# CruiseControlSystemWiringDiagram.net
KiCad netlist of a schematic drawn in EasyEDA
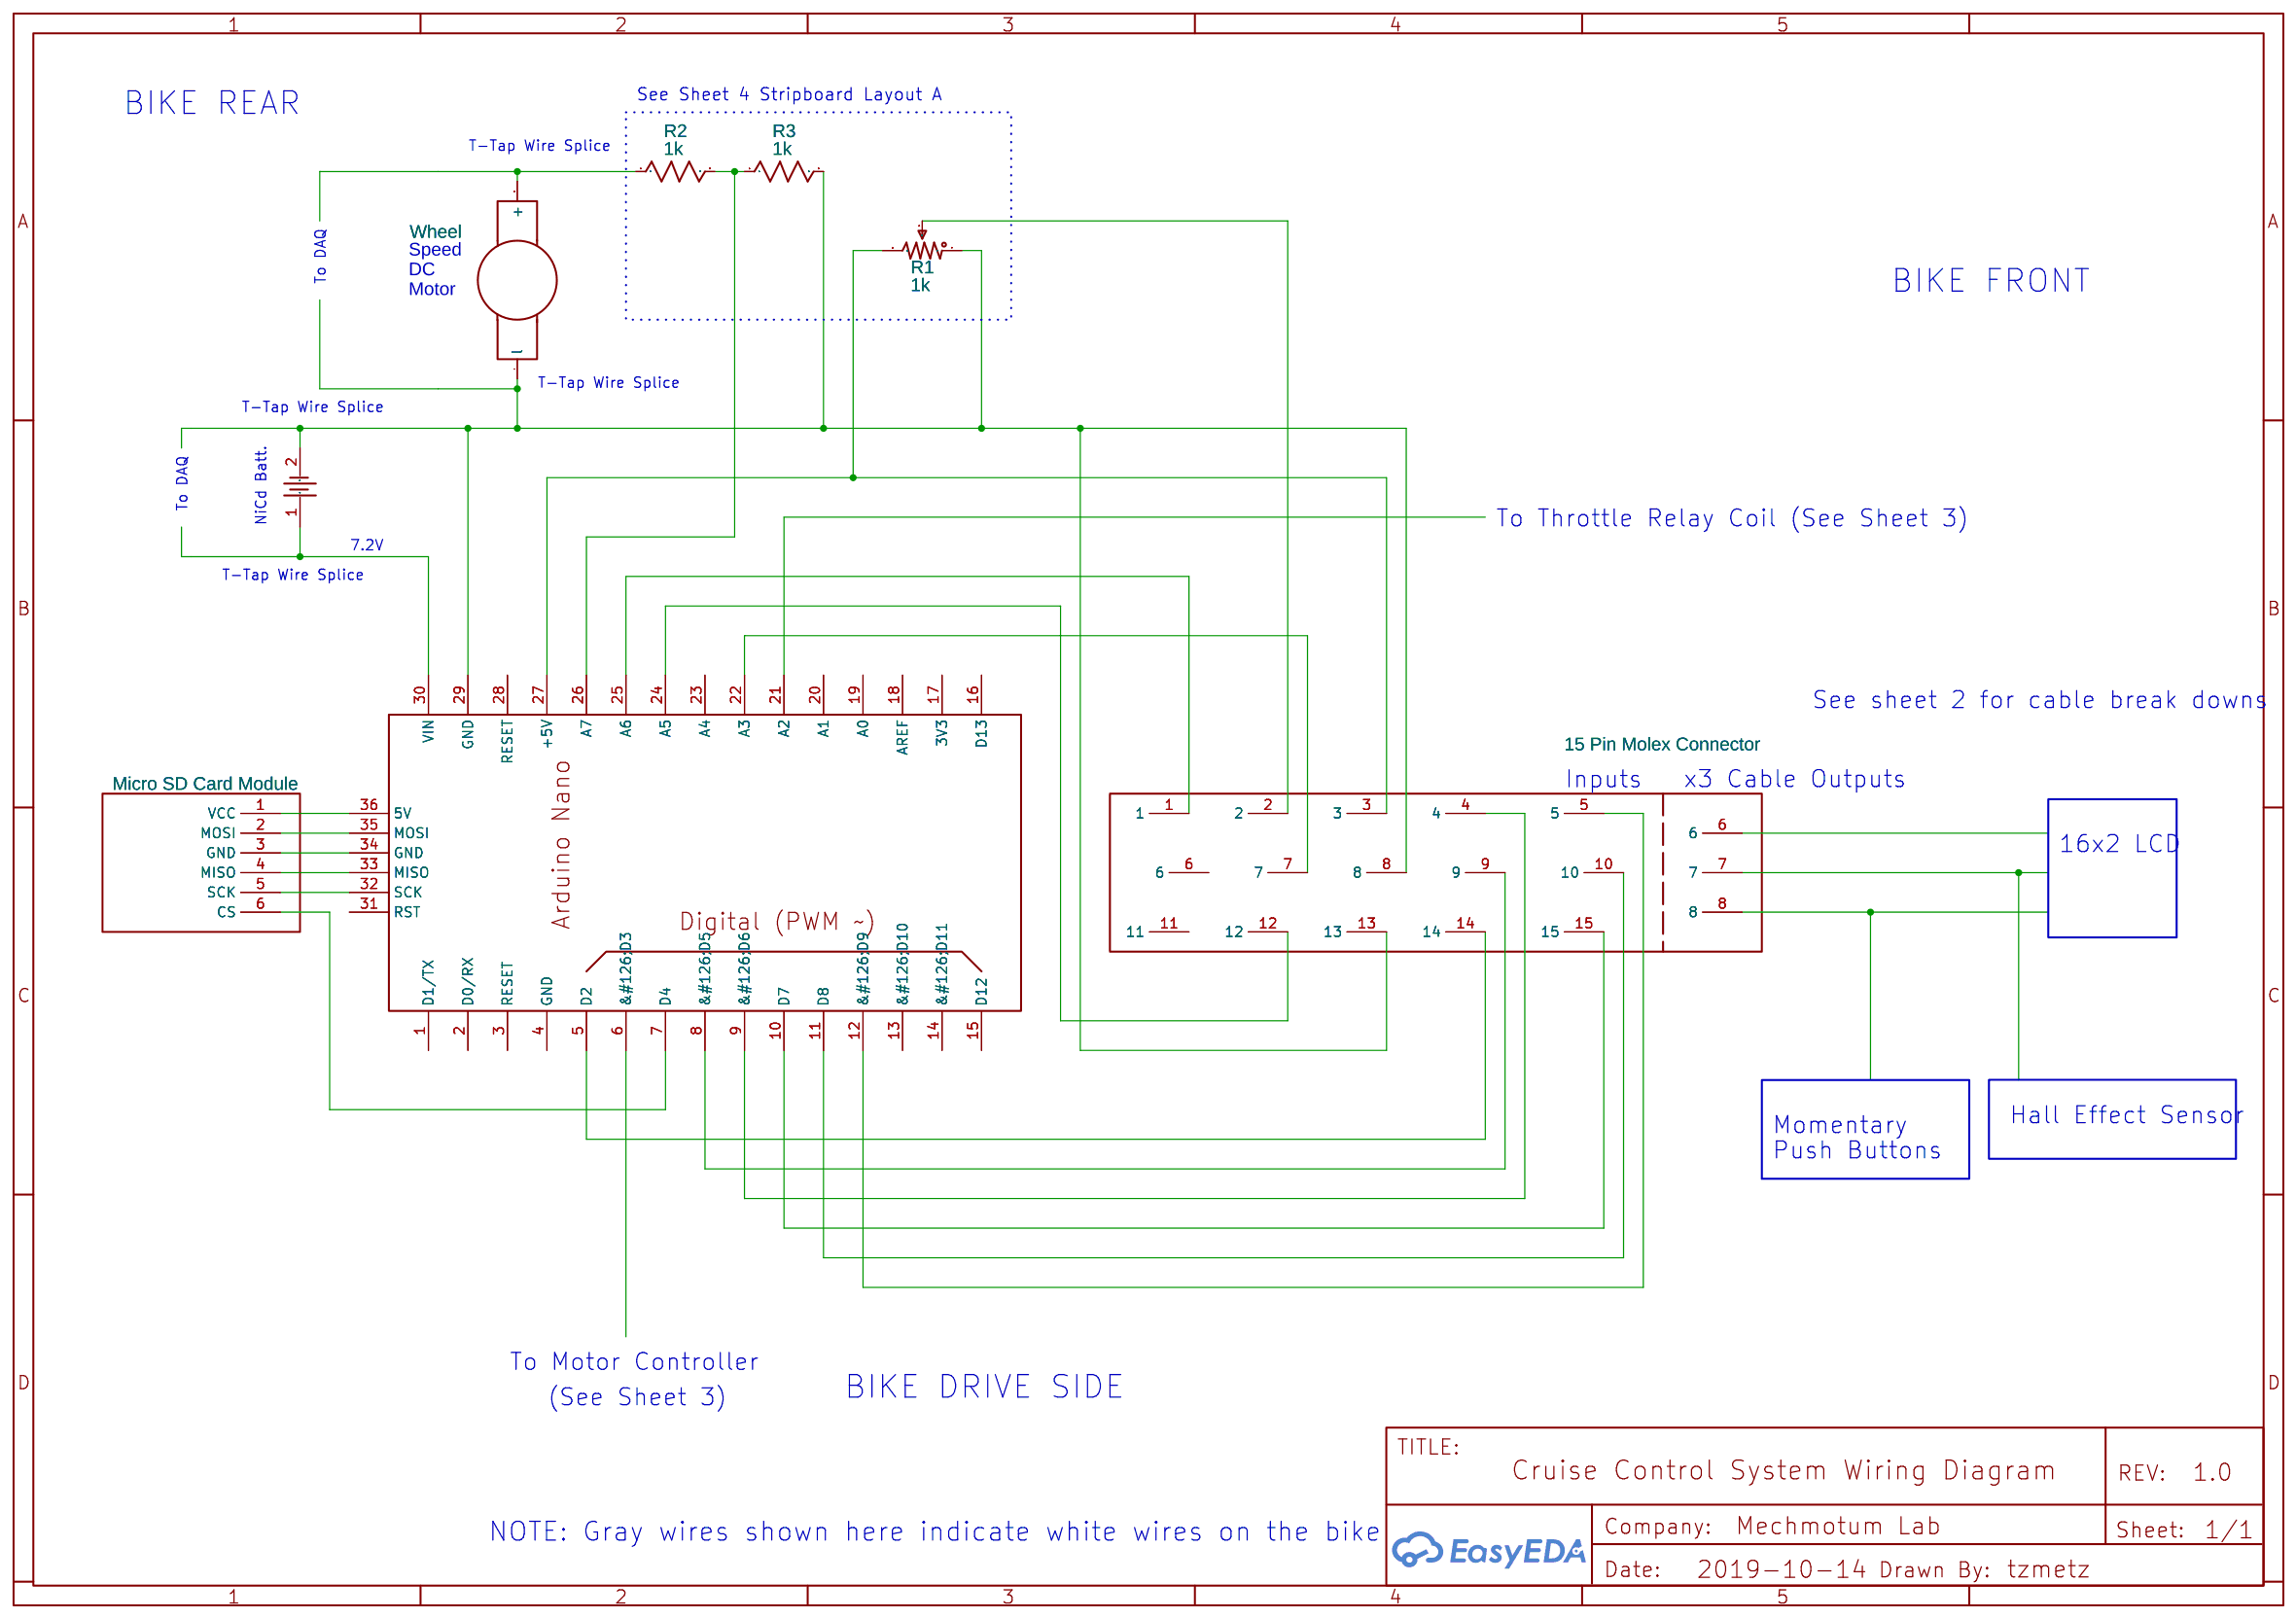
[diagram p0: Sheet_1]
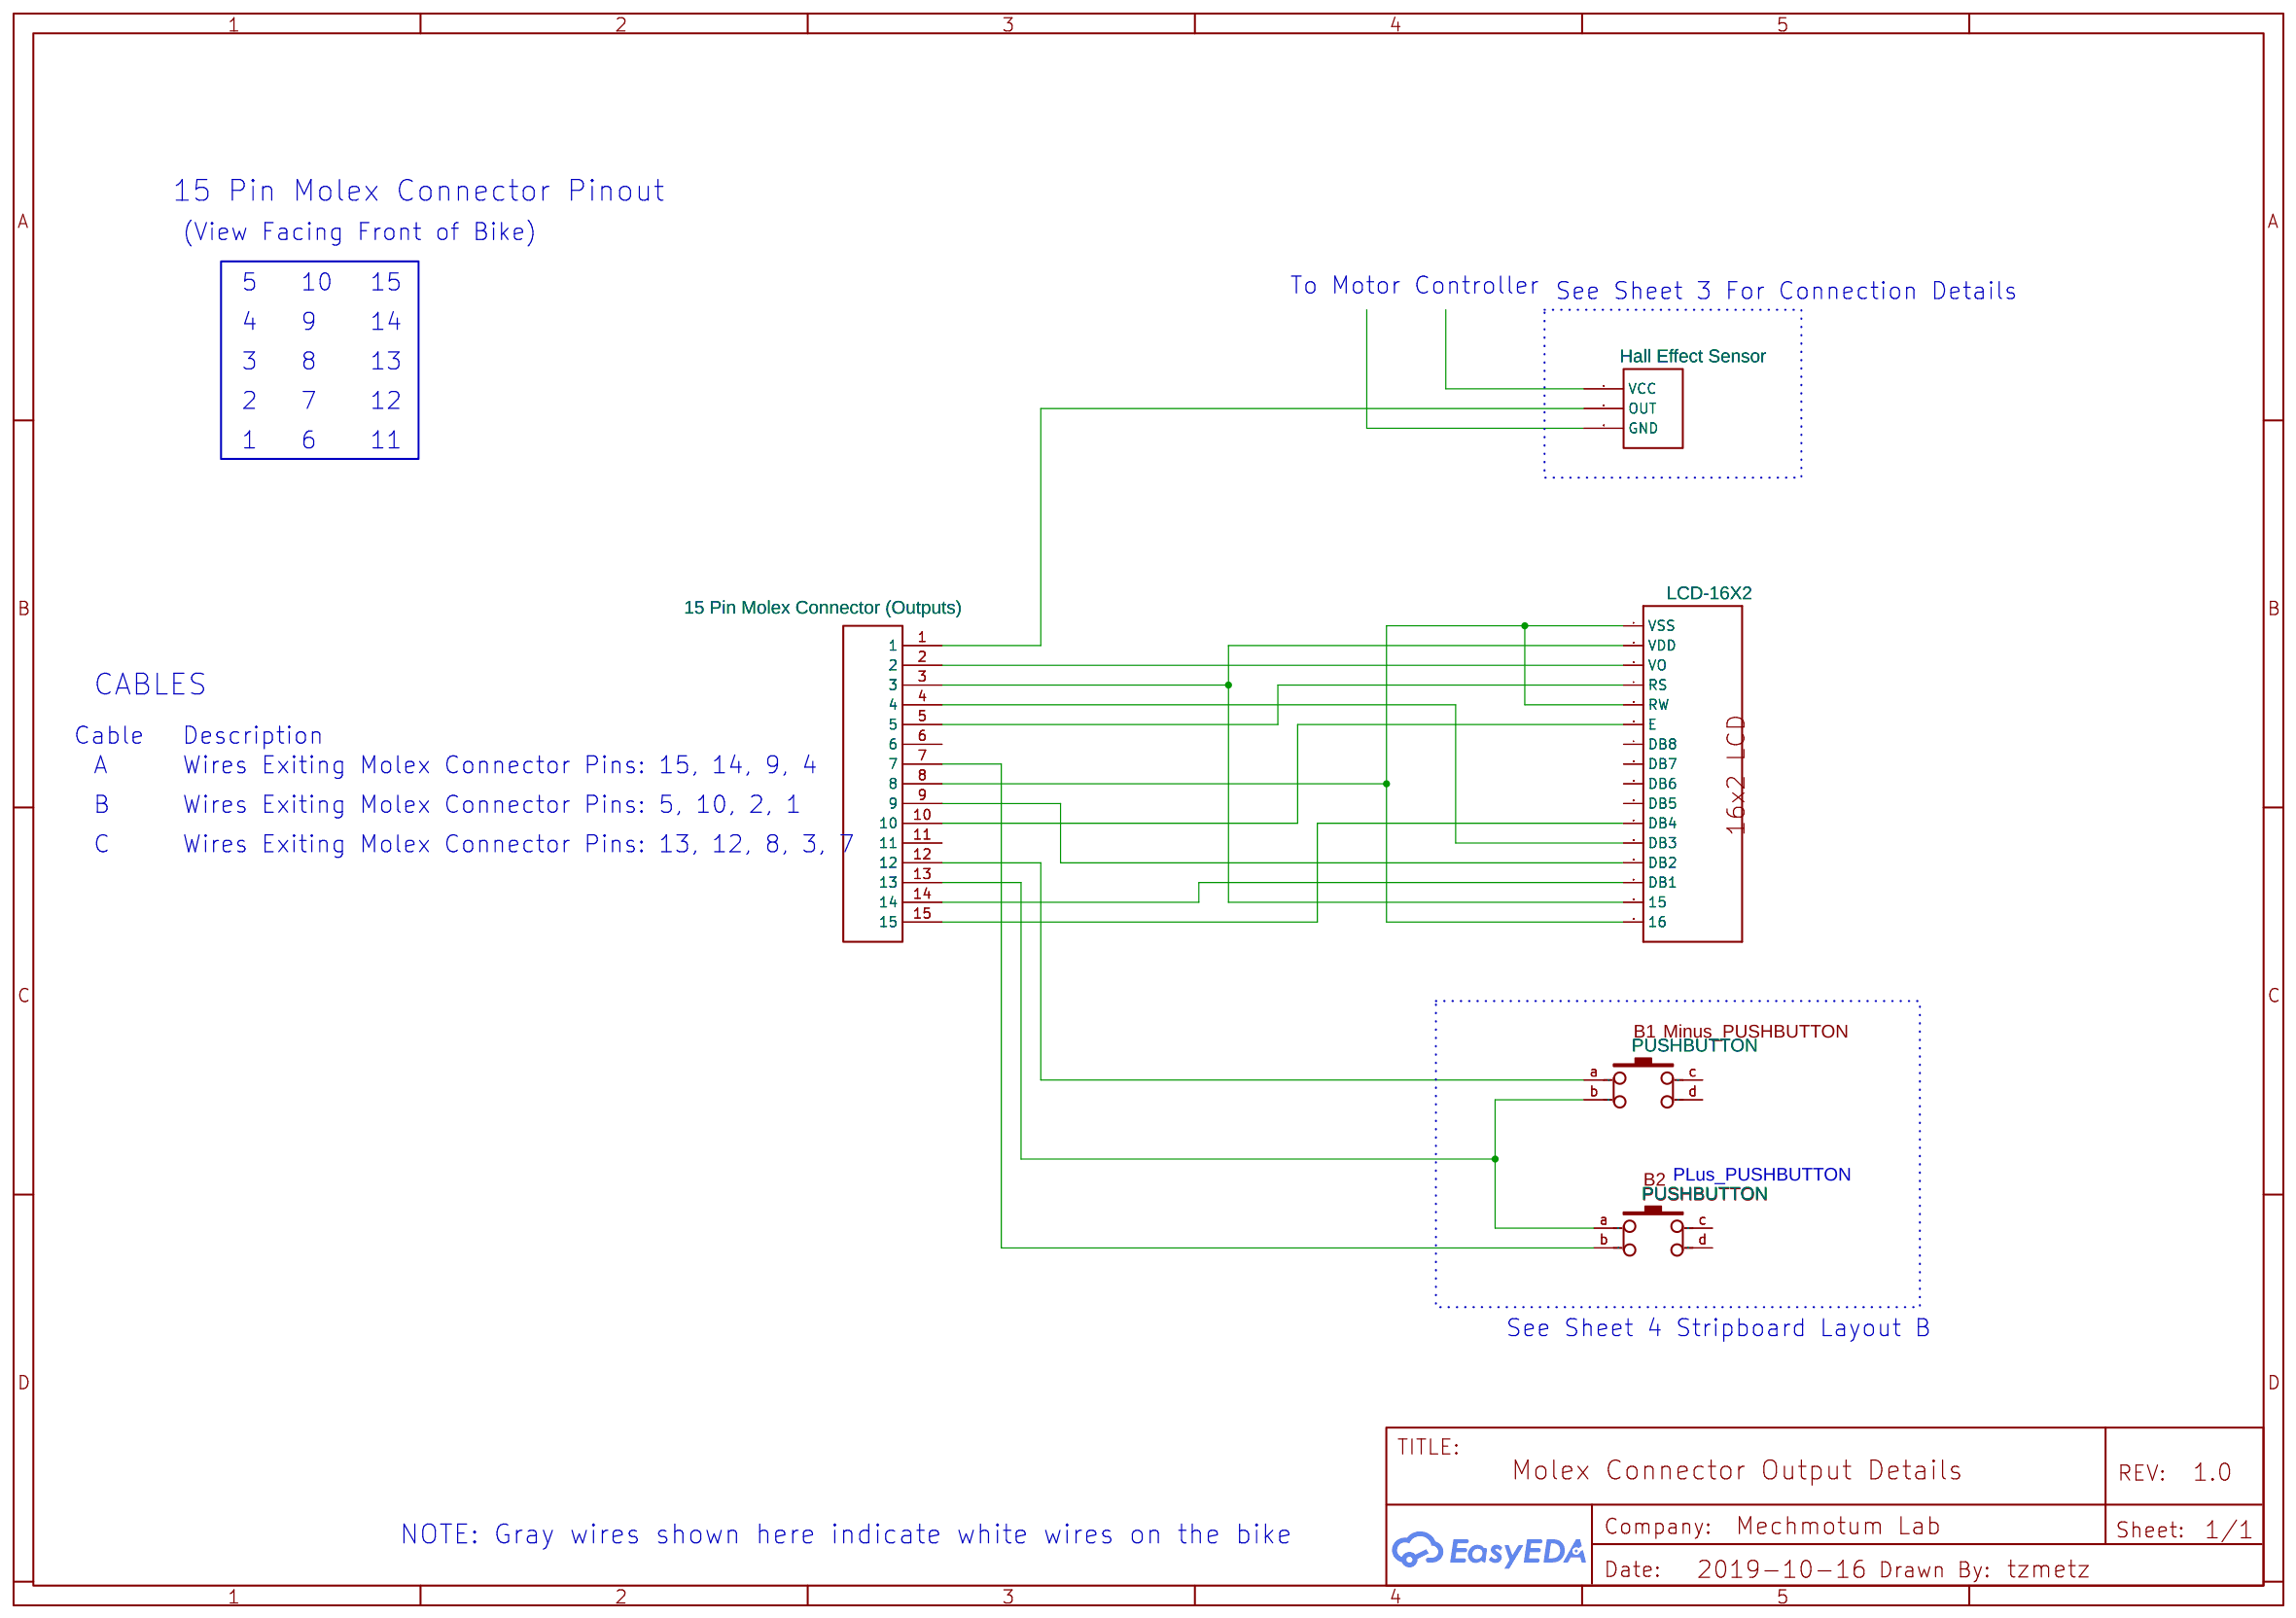
[diagram p1: Sheet_2]
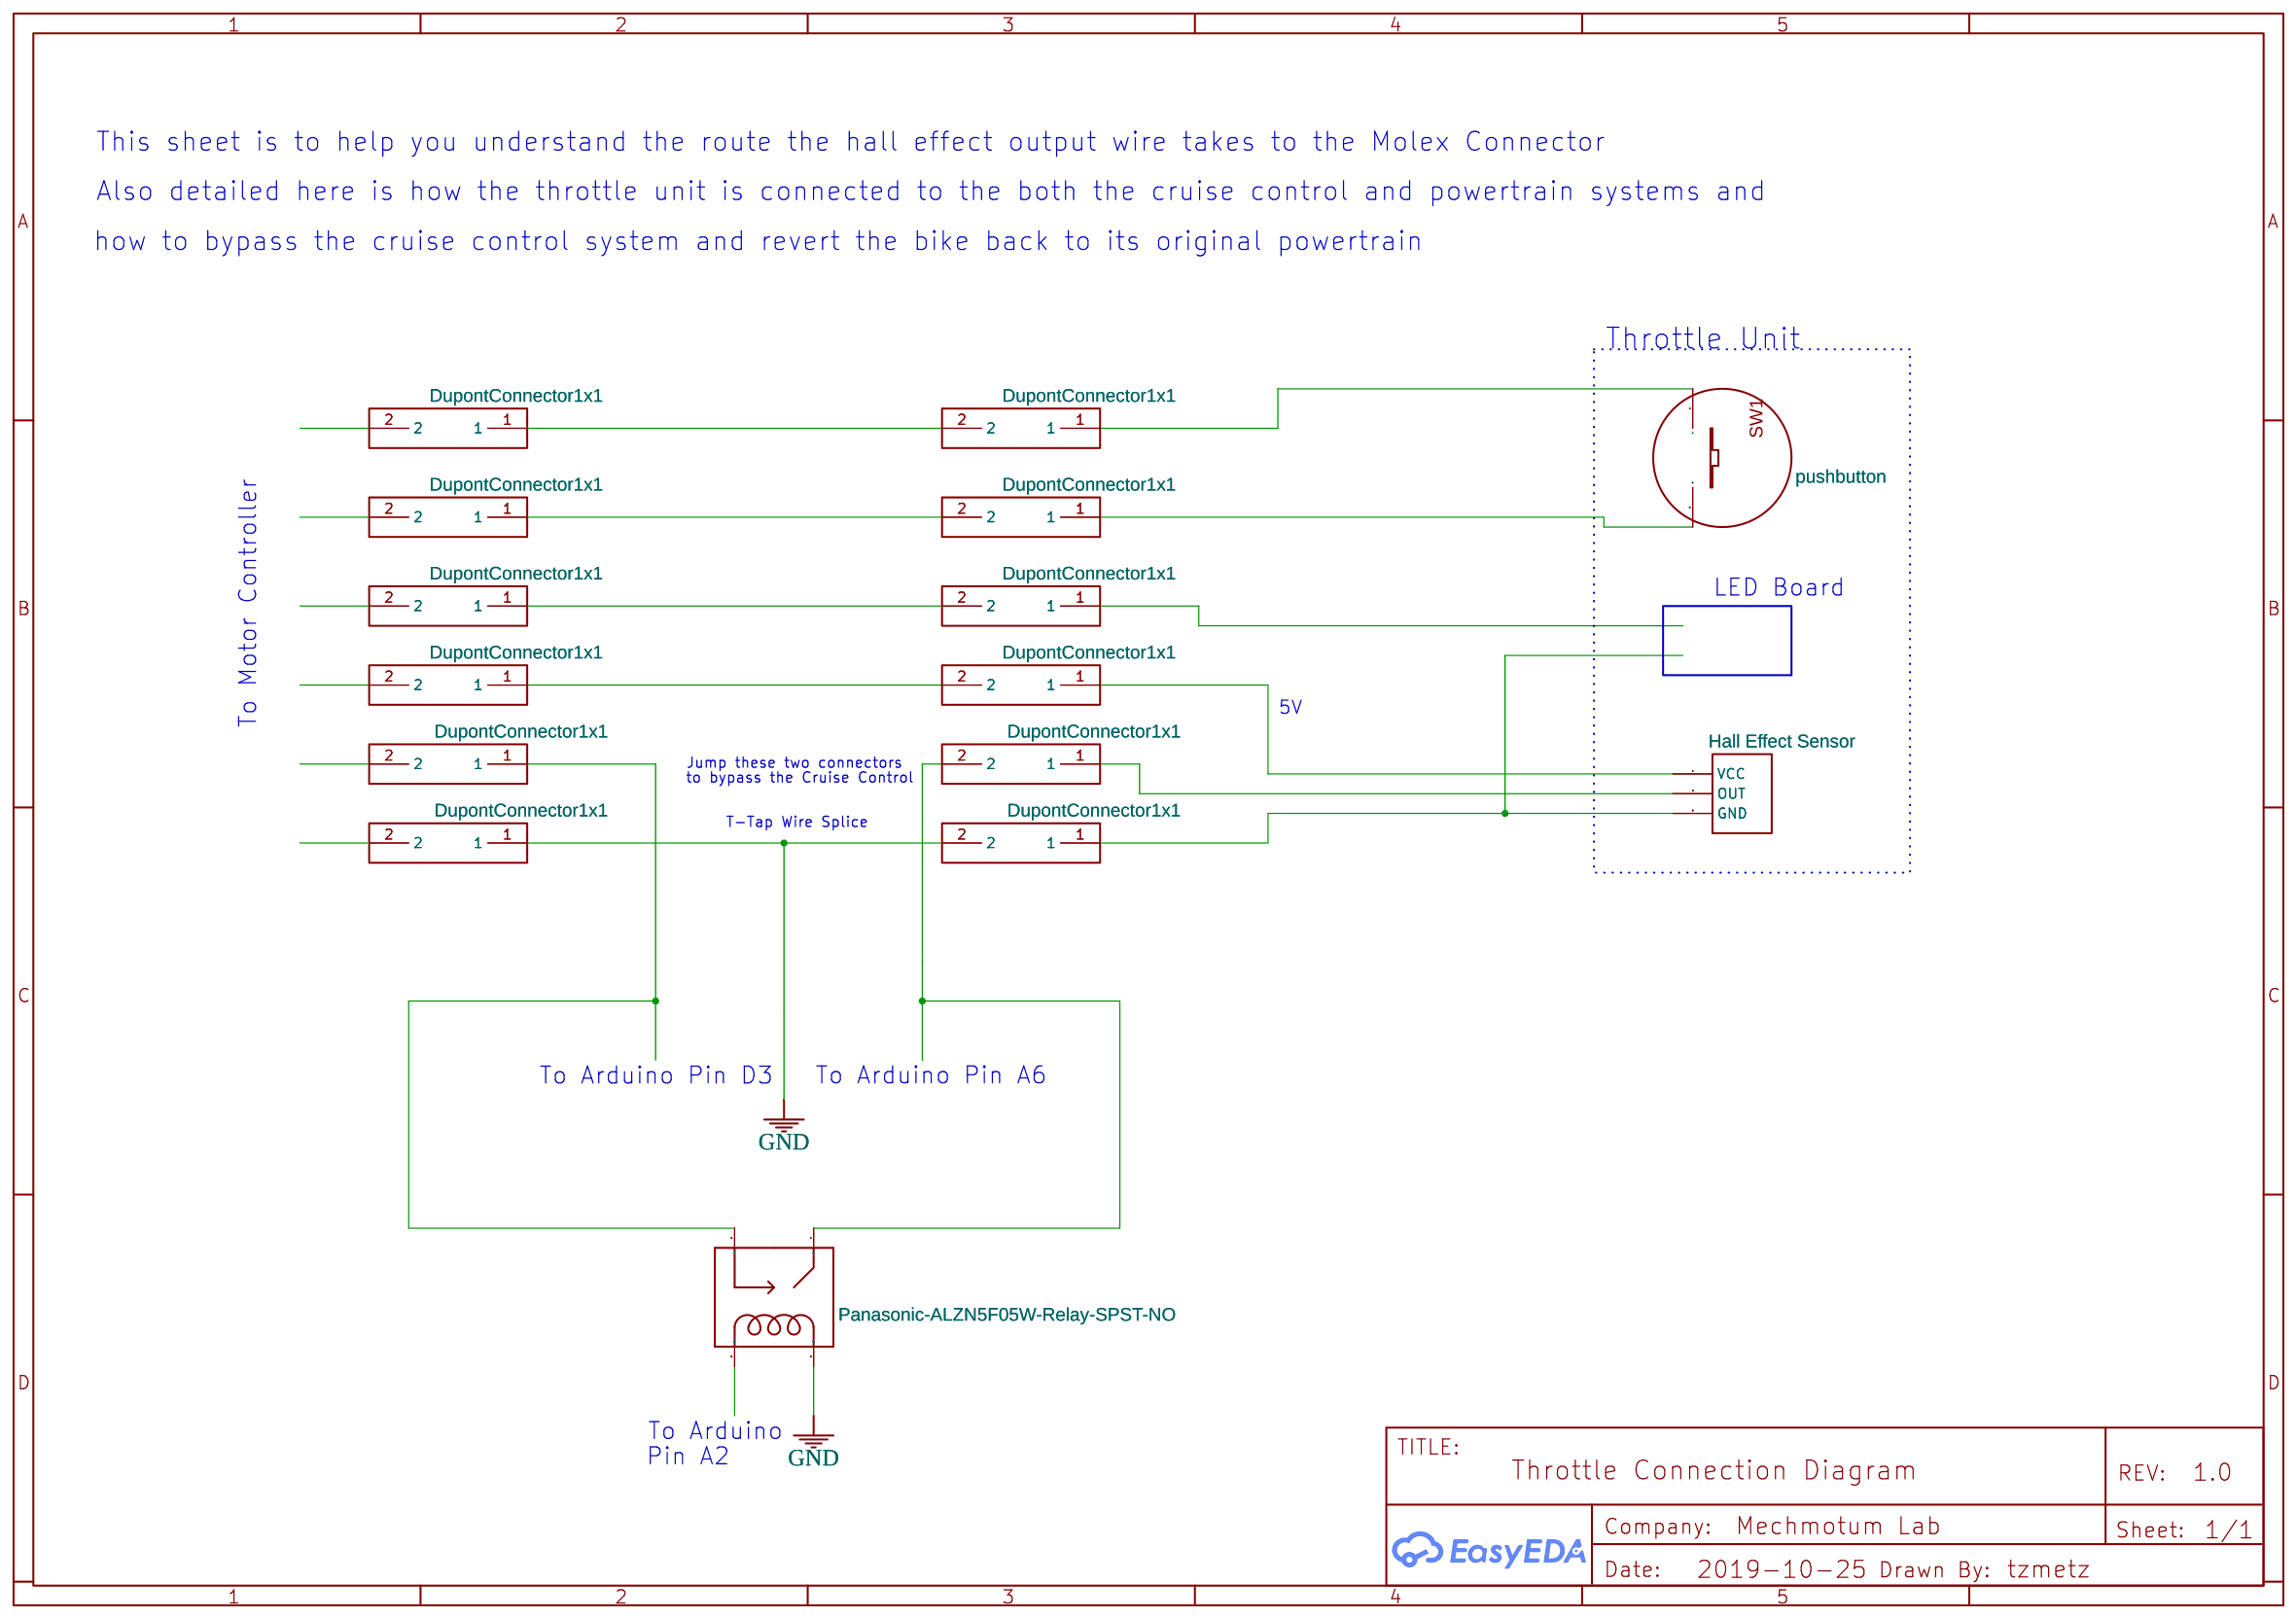
[diagram p2: Sheet_3]
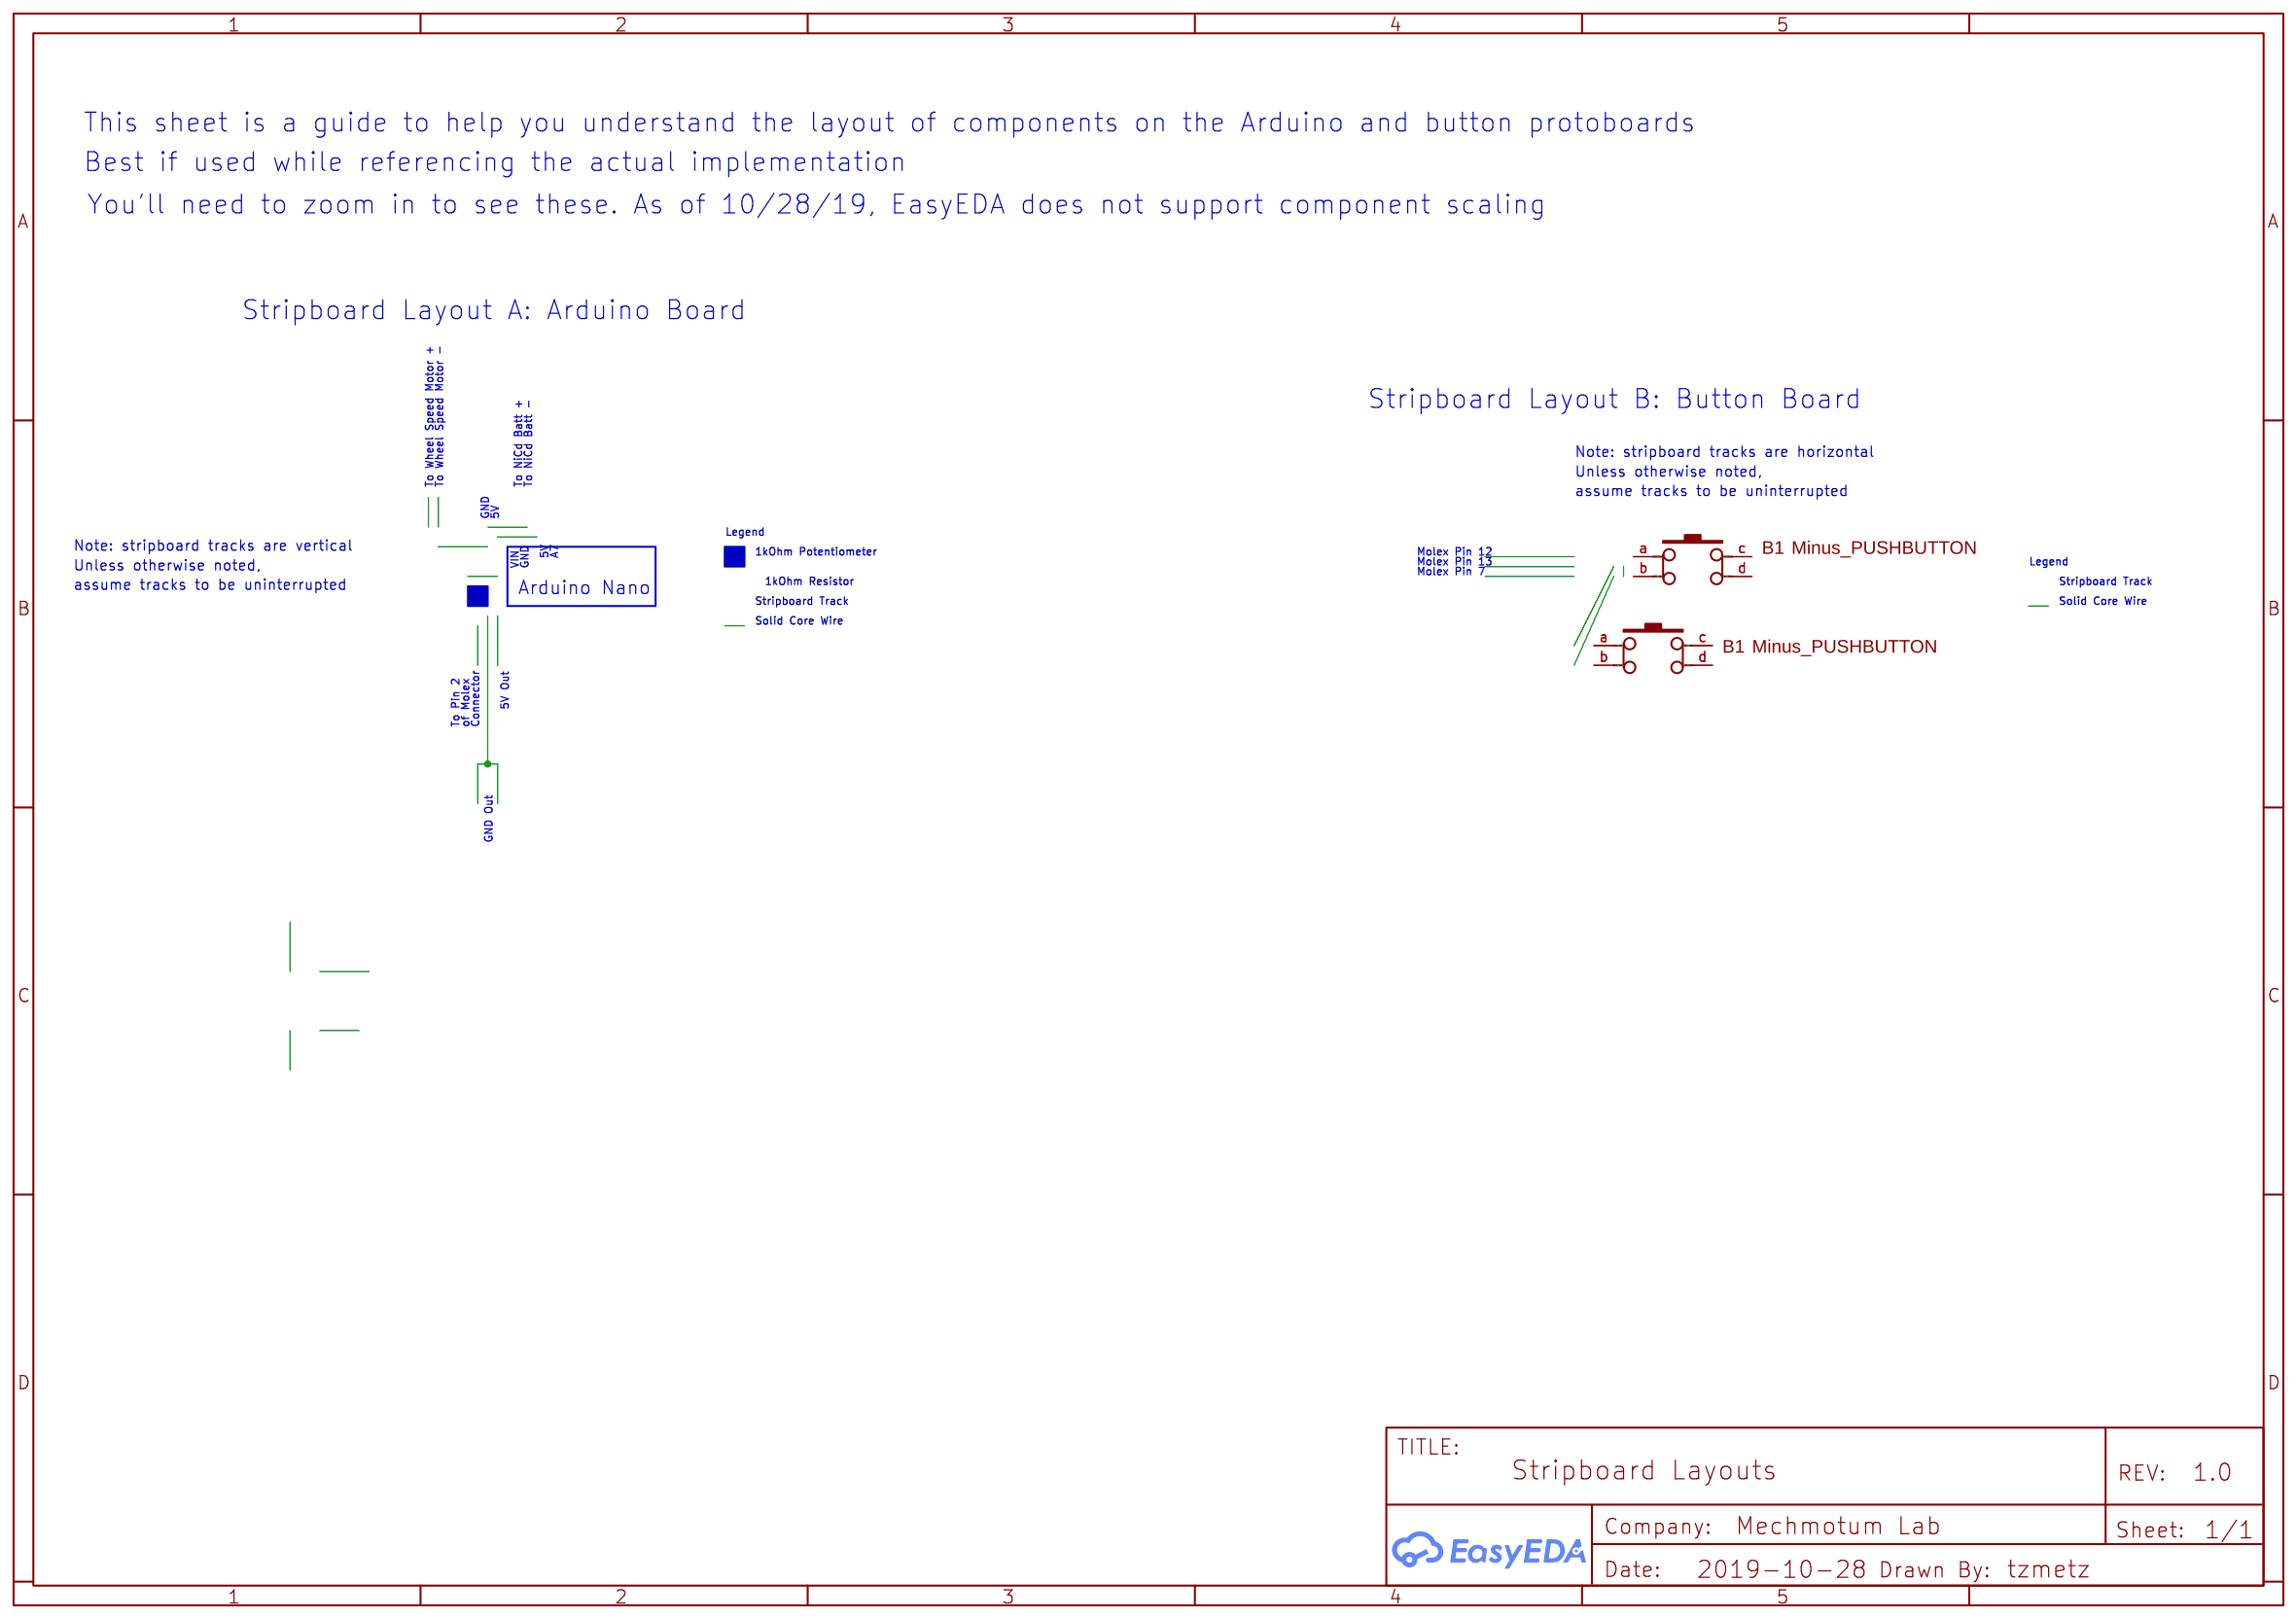
[diagram p3: Sheet_4]
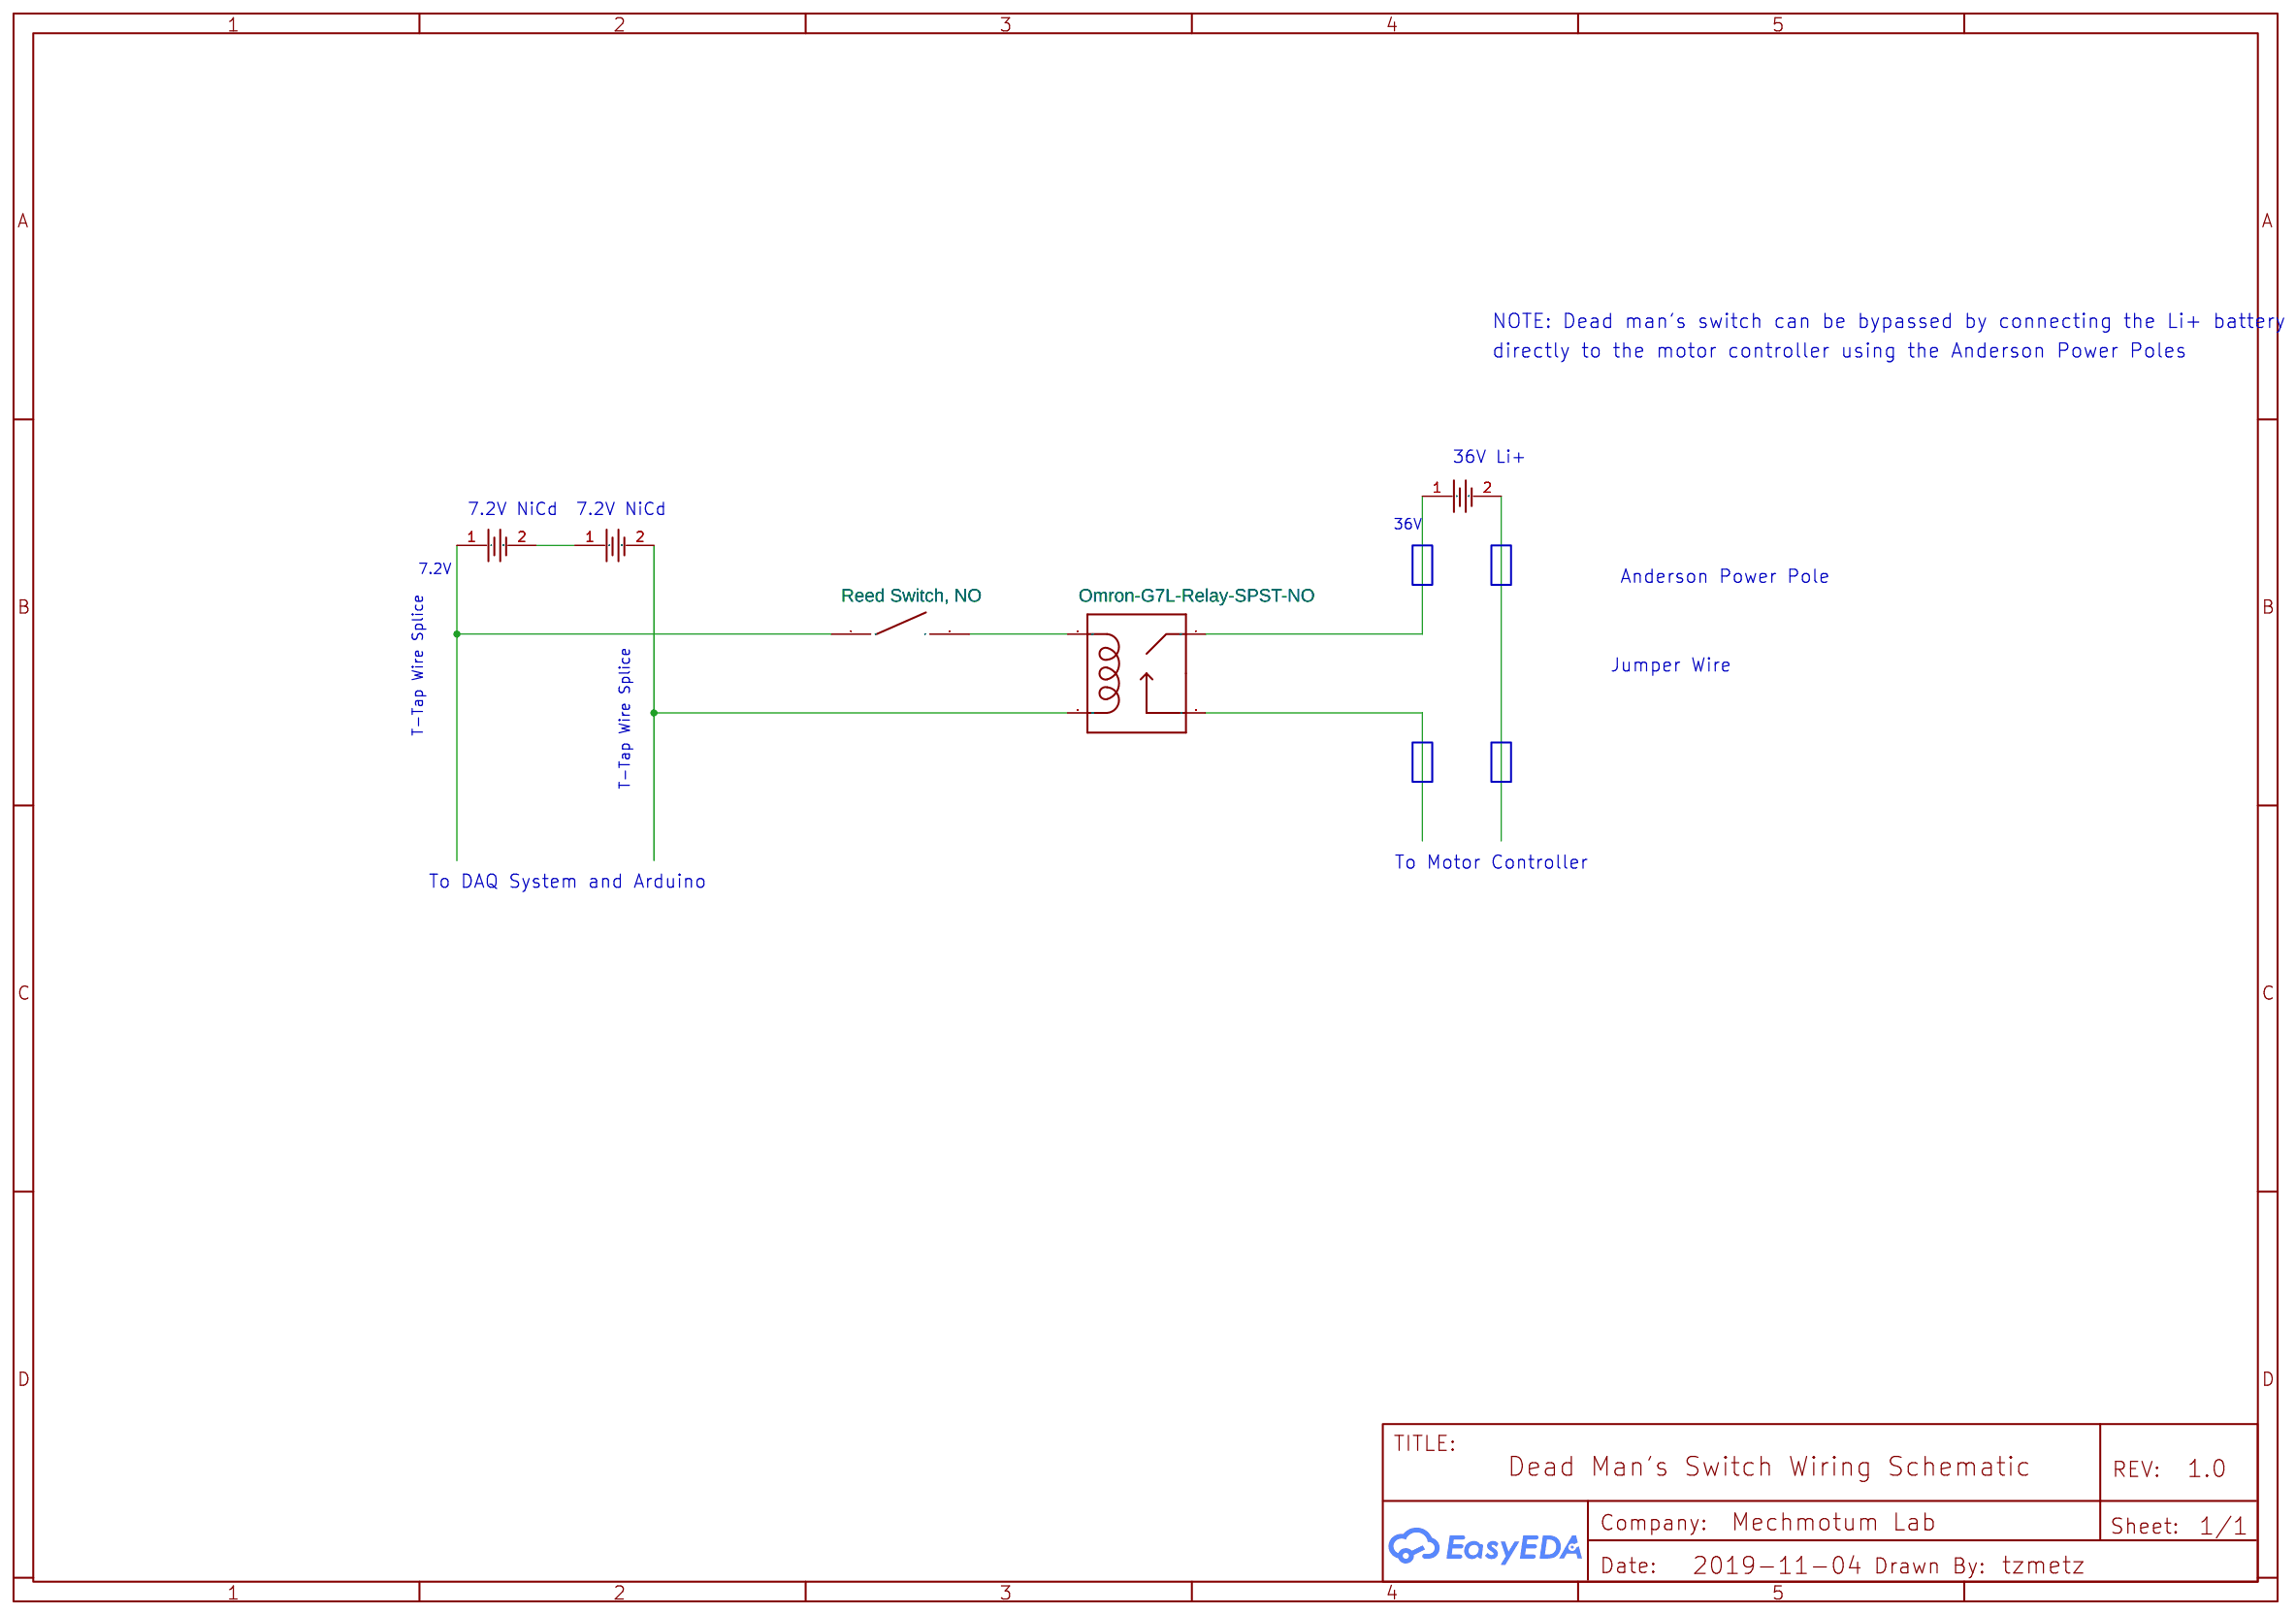
[diagram p4: Sheet_5]

(export (version "E")
  (design (tool "Eeschema 10.0.6"))
  (components
    (comp (ref "B1")
      (value "NiCd Battery 7.2V Line")
      (fields (field (name "BOM_Manufacturer Part") "BS-2-1") (field (name "BOM_Supplier Part") "C70376"))
      (libsource (lib "") (part "Unknown_145_240"))
    )
    (comp (ref "R1")
      (value "1k")
      (fields
        (field (name "BOM_Manufacturer Part") "3386P-1-101LF")
        (field (name "BOM_Supplier Part") "C125022")
      )
      (libsource (lib "") (part "3386P-1-101LF_US"))
    )
    (comp (ref "R2") (value "1k") (libsource (lib "") (part "Res_AXIAL-0.3(1/8W)_US")))
    (comp (ref "R3") (value "1k") (libsource (lib "") (part "Res_AXIAL-0.3(1/8W)_US")))
    (comp (ref "U2")
      (value "ARDUINO_NANO COPY")
      (fields (field (name "BOM_Manufacturer Part") "ARDUINO_NANO_LIVETHINGS"))
      (libsource (lib "") (part "Unknown_350_425"))
    )
    (comp (ref "U5") (value "Wheel") (libsource (lib "") (part "Unknown_255_135")))
    (comp (ref "U8") (value "Micro SD Card Module") (libsource (lib "") (part "Unknown_105_425")))
    (comp (ref "U10") (value "15 Pin Molex Connector") (libsource (lib "") (part "Unknown_635_435")))
    (comp (ref "U1") (value "PUSHBUTTON") (libsource (lib "") (part "Unknown_860_635")))
    (comp (ref "U6") (value "15 Pin Molex Connector (Outputs)") (libsource (lib "") (part "Unknown_450_310")))
    (comp (ref "U11") (value "LCD-16X2") (libsource (lib "") (part "Unknown_845_385")))
    (comp (ref "U12") (value "PUSHBUTTON") (libsource (lib "") (part "Unknown_855_560")))
    (comp (ref "U13") (value "Hall Effect Sensor") (libsource (lib "") (part "Unknown_795_180")))
    (comp (ref "RL2")
      (value "Panasonic-ALZN5F05W-Relay-SPST-NO")
      (libsource (lib "") (part "Unknown_385_645"))
    )
    (comp (ref "U3")
      (value "pushbutton")
      (fields (field (name "BOM_Manufacturer Part") "push button"))
      (libsource (lib "") (part "Unknown_875_220"))
    )
    (comp (ref "U4") (value "Hall Effect Sensor") (libsource (lib "") (part "Unknown_840_375")))
    (comp (ref "U7") (value "DupontConnector1x1") (libsource (lib "") (part "Unknown_510_380")))
    (comp (ref "U9") (value "DupontConnector1x1") (libsource (lib "") (part "Unknown_510_420")))
    (comp (ref "U14") (value "DupontConnector1x1") (libsource (lib "") (part "Unknown_510_300")))
    (comp (ref "U15") (value "DupontConnector1x1") (libsource (lib "") (part "Unknown_510_340")))
    (comp (ref "U16") (value "DupontConnector1x1") (libsource (lib "") (part "Unknown_510_255")))
    (comp (ref "U17") (value "DupontConnector1x1") (libsource (lib "") (part "Unknown_510_210")))
    (comp (ref "U18") (value "DupontConnector1x1") (libsource (lib "") (part "Unknown_220_210")))
    (comp (ref "U19") (value "DupontConnector1x1") (libsource (lib "") (part "Unknown_220_255")))
    (comp (ref "U20") (value "DupontConnector1x1") (libsource (lib "") (part "Unknown_220_340")))
    (comp (ref "U21") (value "DupontConnector1x1") (libsource (lib "") (part "Unknown_220_300")))
    (comp (ref "U22") (value "DupontConnector1x1") (libsource (lib "") (part "Unknown_220_420")))
    (comp (ref "U23") (value "DupontConnector1x1") (libsource (lib "") (part "Unknown_220_380")))
    (comp (ref "U24") (value "PUSHBUTTON") (libsource (lib "") (part "Unknown_880_295")))
    (comp (ref "U25") (value "PUSHBUTTON") (libsource (lib "") (part "Unknown_860_340")))
    (comp (ref "B2")
      (value "BS-2-1")
      (fields (field (name "BOM_Supplier Part") "C70376"))
      (libsource (lib "") (part "Unknown_245_270"))
    )
    (comp (ref "B3")
      (value "BS-2-1")
      (fields (field (name "BOM_Supplier Part") "C70376"))
      (libsource (lib "") (part "Unknown_305_270"))
    )
    (comp (ref "B4")
      (value "BS-2-1")
      (fields (field (name "BOM_Supplier Part") "C70376"))
      (libsource (lib "") (part "Unknown_735_245"))
    )
    (comp (ref "RL1") (value "Omron-G7L-Relay-SPST-NO") (libsource (lib "") (part "Unknown_575_335")))
    (comp (ref "SW1")
      (value "Reed Switch, NO")
      (fields (field (name "BOM_Manufacturer Part") "EVQ22705R") (field (name "BOM_Supplier Part") "C79156"))
      (libsource (lib "") (part "Unknown_450_315"))
    )
  )
  (nets
    (net (code "1") (name "GND") (class "Default")
      (node (ref "RL2") (pin "2") (pinfunction "COIL2_2") (pintype "unspecified"))
      (node (ref "U22") (pin "1") (pinfunction "1_1") (pintype "unspecified"))
      (node (ref "U9") (pin "2") (pinfunction "2_2") (pintype "unspecified"))
    )
    (net (code "2") (name "Net-(B2-Pad1)") (class "Default")
      (node (ref "B2") (pin "1") (pinfunction "1_1") (pintype "input"))
      (node (ref "SW1") (pin "1") (pinfunction "1_1") (pintype "input"))
    )
    (net (code "3") (name "Net-(B2-Pad2)") (class "Default")
      (node (ref "B2") (pin "2") (pinfunction "2_2") (pintype "input"))
      (node (ref "B3") (pin "1") (pinfunction "1_1") (pintype "input"))
    )
    (net (code "4") (name "Net-(R1-Pad2)") (class "Default")
      (node (ref "R1") (pin "2") (pinfunction "2_2") (pintype "unspecified"))
      (node (ref "U10") (pin "2") (pinfunction "2_2") (pintype "unspecified"))
    )
    (net (code "5") (name "Net-(RL1-COIL1)") (class "Default")
      (node (ref "B3") (pin "2") (pinfunction "2_2") (pintype "input"))
      (node (ref "RL1") (pin "5") (pinfunction "COIL1_5") (pintype "unspecified"))
    )
    (net (code "6") (name "Net-(RL1-COIL2)") (class "Default")
      (node (ref "RL1") (pin "2") (pinfunction "COIL2_2") (pintype "unspecified"))
      (node (ref "SW1") (pin "2") (pinfunction "2_2") (pintype "input"))
    )
    (net (code "7") (name "Net-(RL1-MAIN)") (class "Default")
      (node (ref "B4") (pin "1") (pinfunction "1_1") (pintype "input"))
      (node (ref "RL1") (pin "1") (pinfunction "MAIN_1") (pintype "unspecified"))
    )
    (net (code "8") (name "Net-(RL2-MAIN)") (class "Default")
      (node (ref "RL2") (pin "1") (pinfunction "MAIN_1") (pintype "unspecified"))
      (node (ref "U7") (pin "2") (pinfunction "2_2") (pintype "unspecified"))
    )
    (net (code "9") (name "Net-(RL2-NO)") (class "Default")
      (node (ref "RL2") (pin "3") (pinfunction "NO_3") (pintype "unspecified"))
      (node (ref "U23") (pin "1") (pinfunction "1_1") (pintype "unspecified"))
    )
    (net (code "10") (name "Net-(U1-1-Pada)") (class "Default")
      (node (ref "U1") (pin "a") (pinfunction "1_a") (pintype "input"))
      (node (ref "U12") (pin "b") (pinfunction "1_b") (pintype "input"))
      (node (ref "U6") (pin "13") (pinfunction "13_13") (pintype "unspecified"))
    )
    (net (code "11") (name "Net-(U1-1-Padb)") (class "Default")
      (node (ref "U1") (pin "b") (pinfunction "1_b") (pintype "input"))
      (node (ref "U6") (pin "7") (pinfunction "7_7") (pintype "unspecified"))
    )
    (net (code "12") (name "Net-(U2-&#126;D5)") (class "Default")
      (node (ref "U10") (pin "9") (pinfunction "9_9") (pintype "unspecified"))
      (node (ref "U2") (pin "8") (pinfunction "&#126;D5_8") (pintype "unspecified"))
    )
    (net (code "13") (name "Net-(U2-&#126;D6)") (class "Default")
      (node (ref "U10") (pin "4") (pinfunction "4_4") (pintype "unspecified"))
      (node (ref "U2") (pin "9") (pinfunction "&#126;D6_9") (pintype "unspecified"))
    )
    (net (code "14") (name "Net-(U2-&#126;D9)") (class "Default")
      (node (ref "U10") (pin "5") (pinfunction "5_5") (pintype "unspecified"))
      (node (ref "U2") (pin "12") (pinfunction "&#126;D9_12") (pintype "unspecified"))
    )
    (net (code "15") (name "Net-(U2-+5V)") (class "Default")
      (node (ref "R1") (pin "3") (pinfunction "3_3") (pintype "unspecified"))
      (node (ref "U10") (pin "3") (pinfunction "3_3") (pintype "unspecified"))
      (node (ref "U2") (pin "27") (pinfunction "+5V_27") (pintype "unspecified"))
    )
    (net (code "16") (name "Net-(U2-5V)") (class "Default")
      (node (ref "U2") (pin "36") (pinfunction "5V_36") (pintype "unspecified"))
      (node (ref "U8") (pin "1") (pinfunction "VCC_1") (pintype "unspecified"))
    )
    (net (code "17") (name "Net-(U2-A3)") (class "Default")
      (node (ref "U10") (pin "7") (pinfunction "7_7") (pintype "unspecified"))
      (node (ref "U2") (pin "22") (pinfunction "A3_22") (pintype "unspecified"))
    )
    (net (code "18") (name "Net-(U2-A5)") (class "Default")
      (node (ref "U10") (pin "12") (pinfunction "12_12") (pintype "unspecified"))
      (node (ref "U2") (pin "24") (pinfunction "A5_24") (pintype "unspecified"))
    )
    (net (code "19") (name "Net-(U2-A6)") (class "Default")
      (node (ref "U10") (pin "1") (pinfunction "1_1") (pintype "unspecified"))
      (node (ref "U2") (pin "25") (pinfunction "A6_25") (pintype "unspecified"))
    )
    (net (code "20") (name "Net-(U2-A7)") (class "Default")
      (node (ref "R2") (pin "2") (pinfunction "2_2") (pintype "unspecified"))
      (node (ref "R3") (pin "1") (pinfunction "1_1") (pintype "unspecified"))
      (node (ref "U2") (pin "26") (pinfunction "A7_26") (pintype "unspecified"))
    )
    (net (code "21") (name "Net-(U2-D2)") (class "Default")
      (node (ref "U10") (pin "14") (pinfunction "14_14") (pintype "unspecified"))
      (node (ref "U2") (pin "5") (pinfunction "D2_5") (pintype "unspecified"))
    )
    (net (code "22") (name "Net-(U2-D4)") (class "Default")
      (node (ref "U2") (pin "7") (pinfunction "D4_7") (pintype "unspecified"))
      (node (ref "U8") (pin "6") (pinfunction "CS_6") (pintype "unspecified"))
    )
    (net (code "23") (name "Net-(U2-D7)") (class "Default")
      (node (ref "U10") (pin "15") (pinfunction "15_15") (pintype "unspecified"))
      (node (ref "U2") (pin "10") (pinfunction "D7_10") (pintype "unspecified"))
    )
    (net (code "24") (name "Net-(U2-D8)") (class "Default")
      (node (ref "U10") (pin "10") (pinfunction "10_10") (pintype "unspecified"))
      (node (ref "U2") (pin "11") (pinfunction "D8_11") (pintype "unspecified"))
    )
    (net (code "25") (name "Net-(U2-MISO)") (class "Default")
      (node (ref "U2") (pin "33") (pinfunction "MISO_33") (pintype "unspecified"))
      (node (ref "U8") (pin "4") (pinfunction "MISO_4") (pintype "unspecified"))
    )
    (net (code "26") (name "Net-(U2-MOSI)") (class "Default")
      (node (ref "U2") (pin "35") (pinfunction "MOSI_35") (pintype "unspecified"))
      (node (ref "U8") (pin "2") (pinfunction "MOSI_2") (pintype "unspecified"))
    )
    (net (code "27") (name "Net-(U2-SCK)") (class "Default")
      (node (ref "U2") (pin "32") (pinfunction "SCK_32") (pintype "unspecified"))
      (node (ref "U8") (pin "5") (pinfunction "SCK_5") (pintype "unspecified"))
    )
    (net (code "28") (name "Net-(U2-VIN)") (class "Default")
      (node (ref "B1") (pin "1") (pinfunction "1_1") (pintype "input"))
      (node (ref "U2") (pin "30") (pinfunction "VIN_30") (pintype "unspecified"))
    )
    (net (code "29") (name "Net-(U4-GND)") (class "Default")
      (node (ref "U4") (pin "3") (pinfunction "GND_3") (pintype "unspecified"))
      (node (ref "U9") (pin "1") (pinfunction "1_1") (pintype "unspecified"))
    )
    (net (code "30") (name "Net-(U4-OUT)") (class "Default")
      (node (ref "U4") (pin "2") (pinfunction "OUT_2") (pintype "unspecified"))
      (node (ref "U7") (pin "1") (pinfunction "1_1") (pintype "unspecified"))
    )
    (net (code "31") (name "Net-(U4-VCC)") (class "Default")
      (node (ref "U15") (pin "1") (pinfunction "1_1") (pintype "unspecified"))
      (node (ref "U4") (pin "1") (pinfunction "VCC_1") (pintype "unspecified"))
    )
    (net (code "32") (name "Net-(U5-+)") (class "Default")
      (node (ref "R2") (pin "1") (pinfunction "1_1") (pintype "unspecified"))
      (node (ref "U5") (pin "1") (pinfunction "+_1") (pintype "unspecified"))
    )
    (net (code "33") (name "Net-(U5-l)") (class "Default")
      (node (ref "B1") (pin "2") (pinfunction "2_2") (pintype "input"))
      (node (ref "R1") (pin "1") (pinfunction "1_1") (pintype "unspecified"))
      (node (ref "R3") (pin "2") (pinfunction "2_2") (pintype "unspecified"))
      (node (ref "U10") (pin "13") (pinfunction "13_13") (pintype "unspecified"))
      (node (ref "U10") (pin "8") (pinfunction "8_8") (pintype "unspecified"))
      (node (ref "U2") (pin "29") (pinfunction "GND_29") (pintype "unspecified"))
      (node (ref "U5") (pin "-") (pinfunction "l_-") (pintype "unspecified"))
    )
    (net (code "34") (name "Net-(U8-GND)") (class "Default")
      (node (ref "U2") (pin "34") (pinfunction "GND_34") (pintype "unspecified"))
      (node (ref "U8") (pin "3") (pinfunction "GND_3") (pintype "unspecified"))
    )
    (net (code "35") (name "Net-(U11-DB1)") (class "Default")
      (node (ref "U11") (pin "14") (pinfunction "DB1_14") (pintype "unspecified"))
      (node (ref "U6") (pin "14") (pinfunction "14_14") (pintype "unspecified"))
    )
    (net (code "36") (name "Net-(U11-DB2)") (class "Default")
      (node (ref "U11") (pin "13") (pinfunction "DB2_13") (pintype "unspecified"))
      (node (ref "U6") (pin "9") (pinfunction "9_9") (pintype "unspecified"))
    )
    (net (code "37") (name "Net-(U11-DB3)") (class "Default")
      (node (ref "U11") (pin "12") (pinfunction "DB3_12") (pintype "unspecified"))
      (node (ref "U6") (pin "4") (pinfunction "4_4") (pintype "unspecified"))
    )
    (net (code "38") (name "Net-(U11-DB4)") (class "Default")
      (node (ref "U11") (pin "11") (pinfunction "DB4_11") (pintype "unspecified"))
      (node (ref "U6") (pin "15") (pinfunction "15_15") (pintype "unspecified"))
    )
    (net (code "39") (name "Net-(U11-E)") (class "Default")
      (node (ref "U11") (pin "6") (pinfunction "E_6") (pintype "input"))
      (node (ref "U6") (pin "10") (pinfunction "10_10") (pintype "unspecified"))
    )
    (net (code "40") (name "Net-(U11-RS)") (class "Default")
      (node (ref "U11") (pin "4") (pinfunction "RS_4") (pintype "input"))
      (node (ref "U6") (pin "5") (pinfunction "5_5") (pintype "unspecified"))
    )
    (net (code "41") (name "Net-(U11-RW)") (class "Default")
      (node (ref "U11") (pin "1") (pinfunction "VSS_1") (pintype "passive"))
      (node (ref "U11") (pin "16") (pinfunction "16_16") (pintype "passive"))
      (node (ref "U11") (pin "5") (pinfunction "RW_5") (pintype "input"))
      (node (ref "U6") (pin "8") (pinfunction "8_8") (pintype "unspecified"))
    )
    (net (code "42") (name "Net-(U11-VDD)") (class "Default")
      (node (ref "U11") (pin "15") (pinfunction "15_15") (pintype "passive"))
      (node (ref "U11") (pin "2") (pinfunction "VDD_2") (pintype "passive"))
      (node (ref "U6") (pin "3") (pinfunction "3_3") (pintype "unspecified"))
    )
    (net (code "43") (name "Net-(U11-VO)") (class "Default")
      (node (ref "U11") (pin "3") (pinfunction "VO_3") (pintype "unspecified"))
      (node (ref "U6") (pin "2") (pinfunction "2_2") (pintype "unspecified"))
    )
    (net (code "44") (name "Net-(U12-1-Pada)") (class "Default")
      (node (ref "U12") (pin "a") (pinfunction "1_a") (pintype "input"))
      (node (ref "U6") (pin "12") (pinfunction "12_12") (pintype "unspecified"))
    )
    (net (code "45") (name "Net-(U13-OUT)") (class "Default")
      (node (ref "U13") (pin "2") (pinfunction "OUT_2") (pintype "unspecified"))
      (node (ref "U6") (pin "1") (pinfunction "1_1") (pintype "unspecified"))
    )
    (net (code "46") (name "Net-(U14-Pad2)") (class "Default")
      (node (ref "U14") (pin "2") (pinfunction "2_2") (pintype "unspecified"))
      (node (ref "U21") (pin "1") (pinfunction "1_1") (pintype "unspecified"))
    )
    (net (code "47") (name "Net-(U15-Pad2)") (class "Default")
      (node (ref "U15") (pin "2") (pinfunction "2_2") (pintype "unspecified"))
      (node (ref "U20") (pin "1") (pinfunction "1_1") (pintype "unspecified"))
    )
    (net (code "48") (name "Net-(U16-Pad1)") (class "Default")
      (node (ref "U16") (pin "1") (pinfunction "1_1") (pintype "unspecified"))
      (node (ref "U3") (pin "2") (pinfunction "2_2") (pintype "input"))
    )
    (net (code "49") (name "Net-(U16-Pad2)") (class "Default")
      (node (ref "U16") (pin "2") (pinfunction "2_2") (pintype "unspecified"))
      (node (ref "U19") (pin "1") (pinfunction "1_1") (pintype "unspecified"))
    )
    (net (code "50") (name "Net-(U17-Pad1)") (class "Default")
      (node (ref "U17") (pin "1") (pinfunction "1_1") (pintype "unspecified"))
      (node (ref "U3") (pin "1") (pinfunction "1_1") (pintype "input"))
    )
    (net (code "51") (name "Net-(U17-Pad2)") (class "Default")
      (node (ref "U17") (pin "2") (pinfunction "2_2") (pintype "unspecified"))
      (node (ref "U18") (pin "1") (pinfunction "1_1") (pintype "unspecified"))
    )
    (net (code "52") (name "unconnected-(B4-Pad2)") (class "Default")
      (node (ref "B4") (pin "2") (pinfunction "2_2") (pintype "input"))
    )
    (net (code "53") (name "unconnected-(RL1-NO-Pad3)") (class "Default")
      (node (ref "RL1") (pin "3") (pinfunction "NO_3") (pintype "unspecified"))
    )
    (net (code "54") (name "unconnected-(RL2-COIL1-Pad5)") (class "Default")
      (node (ref "RL2") (pin "5") (pinfunction "COIL1_5") (pintype "unspecified"))
    )
    (net (code "55") (name "unconnected-(U1-2-Padd)") (class "Default")
      (node (ref "U1") (pin "d") (pinfunction "2_d") (pintype "input"))
    )
    (net (code "56") (name "unconnected-(U1-3-Padc)") (class "Default")
      (node (ref "U1") (pin "c") (pinfunction "3_c") (pintype "input"))
    )
    (net (code "57") (name "unconnected-(U2-&#126;D3-Pad6)") (class "Default")
      (node (ref "U2") (pin "6") (pinfunction "&#126;D3_6") (pintype "unspecified"))
    )
    (net (code "58") (name "unconnected-(U2-&#126;D10-Pad13)") (class "Default")
      (node (ref "U2") (pin "13") (pinfunction "&#126;D10_13") (pintype "unspecified"))
    )
    (net (code "59") (name "unconnected-(U2-&#126;D11-Pad14)") (class "Default")
      (node (ref "U2") (pin "14") (pinfunction "&#126;D11_14") (pintype "unspecified"))
    )
    (net (code "60") (name "unconnected-(U2-3V3-Pad17)") (class "Default")
      (node (ref "U2") (pin "17") (pinfunction "3V3_17") (pintype "unspecified"))
    )
    (net (code "61") (name "unconnected-(U2-A0-Pad19)") (class "Default")
      (node (ref "U2") (pin "19") (pinfunction "A0_19") (pintype "unspecified"))
    )
    (net (code "62") (name "unconnected-(U2-A1-Pad20)") (class "Default")
      (node (ref "U2") (pin "20") (pinfunction "A1_20") (pintype "unspecified"))
    )
    (net (code "63") (name "unconnected-(U2-A2-Pad21)") (class "Default")
      (node (ref "U2") (pin "21") (pinfunction "A2_21") (pintype "unspecified"))
    )
    (net (code "64") (name "unconnected-(U2-A4-Pad23)") (class "Default")
      (node (ref "U2") (pin "23") (pinfunction "A4_23") (pintype "unspecified"))
    )
    (net (code "65") (name "unconnected-(U2-AREF-Pad18)") (class "Default")
      (node (ref "U2") (pin "18") (pinfunction "AREF_18") (pintype "unspecified"))
    )
    (net (code "66") (name "unconnected-(U2-D0{slash}RX-Pad2)") (class "Default")
      (node (ref "U2") (pin "2") (pinfunction "D0/RX_2") (pintype "unspecified"))
    )
    (net (code "67") (name "unconnected-(U2-D1{slash}TX-Pad1)") (class "Default")
      (node (ref "U2") (pin "1") (pinfunction "D1/TX_1") (pintype "unspecified"))
    )
    (net (code "68") (name "unconnected-(U2-D12-Pad15)") (class "Default")
      (node (ref "U2") (pin "15") (pinfunction "D12_15") (pintype "unspecified"))
    )
    (net (code "69") (name "unconnected-(U2-D13-Pad16)") (class "Default")
      (node (ref "U2") (pin "16") (pinfunction "D13_16") (pintype "unspecified"))
    )
    (net (code "70") (name "unconnected-(U2-GND-Pad4)") (class "Default")
      (node (ref "U2") (pin "4") (pinfunction "GND_4") (pintype "unspecified"))
    )
    (net (code "71") (name "unconnected-(U2-RESET-Pad3)") (class "Default")
      (node (ref "U2") (pin "3") (pinfunction "RESET_3") (pintype "unspecified"))
    )
    (net (code "72") (name "unconnected-(U2-RESET-Pad28)") (class "Default")
      (node (ref "U2") (pin "28") (pinfunction "RESET_28") (pintype "unspecified"))
    )
    (net (code "73") (name "unconnected-(U2-RST-Pad31)") (class "Default")
      (node (ref "U2") (pin "31") (pinfunction "RST_31") (pintype "unspecified"))
    )
    (net (code "74") (name "unconnected-(U6-Pad6)") (class "Default")
      (node (ref "U6") (pin "6") (pinfunction "6_6") (pintype "unspecified"))
    )
    (net (code "75") (name "unconnected-(U6-Pad11)") (class "Default")
      (node (ref "U6") (pin "11") (pinfunction "11_11") (pintype "unspecified"))
    )
    (net (code "76") (name "unconnected-(U10-Pad6)") (class "Default")
      (node (ref "U10") (pin "6") (pinfunction "6_6") (pintype "unspecified"))
    )
    (net (code "77") (name "unconnected-(U10-Pad6)_1") (class "Default")
      (node (ref "U10") (pin "6") (pinfunction "6_6") (pintype "unspecified"))
    )
    (net (code "78") (name "unconnected-(U10-Pad7)") (class "Default")
      (node (ref "U10") (pin "7") (pinfunction "7_7") (pintype "unspecified"))
    )
    (net (code "79") (name "unconnected-(U10-Pad8)") (class "Default")
      (node (ref "U10") (pin "8") (pinfunction "8_8") (pintype "unspecified"))
    )
    (net (code "80") (name "unconnected-(U10-Pad11)") (class "Default")
      (node (ref "U10") (pin "11") (pinfunction "11_11") (pintype "unspecified"))
    )
    (net (code "81") (name "unconnected-(U11-DB5-Pad10)") (class "Default")
      (node (ref "U11") (pin "10") (pinfunction "DB5_10") (pintype "unspecified"))
    )
    (net (code "82") (name "unconnected-(U11-DB6-Pad9)") (class "Default")
      (node (ref "U11") (pin "9") (pinfunction "DB6_9") (pintype "unspecified"))
    )
    (net (code "83") (name "unconnected-(U11-DB7-Pad8)") (class "Default")
      (node (ref "U11") (pin "8") (pinfunction "DB7_8") (pintype "unspecified"))
    )
    (net (code "84") (name "unconnected-(U11-DB8-Pad7)") (class "Default")
      (node (ref "U11") (pin "7") (pinfunction "DB8_7") (pintype "unspecified"))
    )
    (net (code "85") (name "unconnected-(U12-2-Padd)") (class "Default")
      (node (ref "U12") (pin "d") (pinfunction "2_d") (pintype "input"))
    )
    (net (code "86") (name "unconnected-(U12-3-Padc)") (class "Default")
      (node (ref "U12") (pin "c") (pinfunction "3_c") (pintype "input"))
    )
    (net (code "87") (name "unconnected-(U13-GND-Pad3)") (class "Default")
      (node (ref "U13") (pin "3") (pinfunction "GND_3") (pintype "unspecified"))
    )
    (net (code "88") (name "unconnected-(U13-VCC-Pad1)") (class "Default")
      (node (ref "U13") (pin "1") (pinfunction "VCC_1") (pintype "unspecified"))
    )
    (net (code "89") (name "unconnected-(U14-Pad1)") (class "Default")
      (node (ref "U14") (pin "1") (pinfunction "1_1") (pintype "unspecified"))
    )
    (net (code "90") (name "unconnected-(U18-Pad2)") (class "Default")
      (node (ref "U18") (pin "2") (pinfunction "2_2") (pintype "unspecified"))
    )
    (net (code "91") (name "unconnected-(U19-Pad2)") (class "Default")
      (node (ref "U19") (pin "2") (pinfunction "2_2") (pintype "unspecified"))
    )
    (net (code "92") (name "unconnected-(U20-Pad2)") (class "Default")
      (node (ref "U20") (pin "2") (pinfunction "2_2") (pintype "unspecified"))
    )
    (net (code "93") (name "unconnected-(U21-Pad2)") (class "Default")
      (node (ref "U21") (pin "2") (pinfunction "2_2") (pintype "unspecified"))
    )
    (net (code "94") (name "unconnected-(U22-Pad2)") (class "Default")
      (node (ref "U22") (pin "2") (pinfunction "2_2") (pintype "unspecified"))
    )
    (net (code "95") (name "unconnected-(U23-Pad2)") (class "Default")
      (node (ref "U23") (pin "2") (pinfunction "2_2") (pintype "unspecified"))
    )
    (net (code "96") (name "unconnected-(U24-1-Pada)") (class "Default")
      (node (ref "U24") (pin "a") (pinfunction "1_a") (pintype "input"))
    )
    (net (code "97") (name "unconnected-(U24-1-Padb)") (class "Default")
      (node (ref "U24") (pin "b") (pinfunction "1_b") (pintype "input"))
    )
    (net (code "98") (name "unconnected-(U24-2-Padd)") (class "Default")
      (node (ref "U24") (pin "d") (pinfunction "2_d") (pintype "input"))
    )
    (net (code "99") (name "unconnected-(U24-3-Padc)") (class "Default")
      (node (ref "U24") (pin "c") (pinfunction "3_c") (pintype "input"))
    )
    (net (code "100") (name "unconnected-(U25-1-Pada)") (class "Default")
      (node (ref "U25") (pin "a") (pinfunction "1_a") (pintype "input"))
    )
    (net (code "101") (name "unconnected-(U25-1-Padb)") (class "Default")
      (node (ref "U25") (pin "b") (pinfunction "1_b") (pintype "input"))
    )
    (net (code "102") (name "unconnected-(U25-2-Padd)") (class "Default")
      (node (ref "U25") (pin "d") (pinfunction "2_d") (pintype "input"))
    )
    (net (code "103") (name "unconnected-(U25-3-Padc)") (class "Default")
      (node (ref "U25") (pin "c") (pinfunction "3_c") (pintype "input"))
    )
  )
)
